# BRIDGE-ACCELEROMETER.net
KiCad netlist of a schematic drawn in Altium Designer
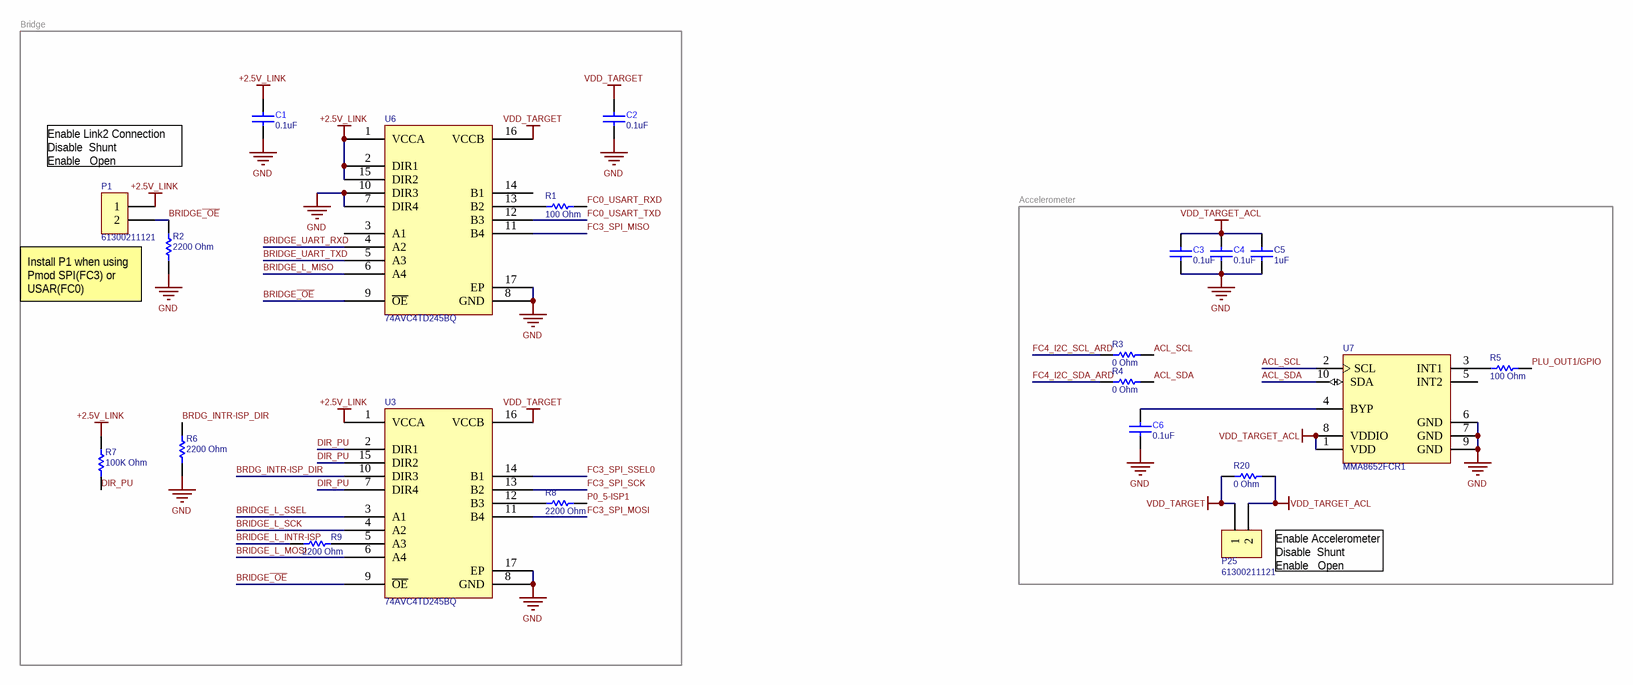
[diagram p0: BRIDGE-ACCELEROMETER.SchDoc]

(export (version "E")
  (design (tool "Eeschema 10.0.6"))
  (components
    (comp (ref "C1")
      (value "0.1uF")
      (footprint "CAPC1005")
      (description "Capacitor, Yageo, Ceramic, 0.1uF 10% 16V 0402 (1005) X7R")
      (fields
        (field (name "TOLERANCE") "10 %")
        (field (name "Comment") "CC0402KRX7R7BB104")
        (field (name "PUBLISHER") "Altium")
      )
      (libsource (lib "Altium Content Vault") (part "CMP-0001-00074-1"))
    )
    (comp (ref "C2")
      (value "0.1uF")
      (footprint "CAPC1005")
      (description "Capacitor, Yageo, Ceramic, 0.1uF 10% 16V 0402 (1005) X7R")
      (fields
        (field (name "TOLERANCE") "10 %")
        (field (name "Comment") "CC0402KRX7R7BB104")
        (field (name "PUBLISHER") "Altium")
      )
      (libsource (lib "Altium Content Vault") (part "CMP-0001-00074-1"))
    )
    (comp (ref "C3")
      (value "0.1uF")
      (footprint "CAPC1005")
      (description "Capacitor, Yageo, Ceramic, 0.1uF 10% 16V 0402 (1005) X7R")
      (fields
        (field (name "TOLERANCE") "10 %")
        (field (name "Comment") "CC0402KRX7R7BB104")
        (field (name "PUBLISHER") "Altium")
      )
      (libsource (lib "Altium Content Vault") (part "CMP-0001-00074-1"))
    )
    (comp (ref "C4")
      (value "0.1uF")
      (footprint "CAPC1005")
      (description "Capacitor, Yageo, Ceramic, 0.1uF 10% 16V 0402 (1005) X7R")
      (fields
        (field (name "TOLERANCE") "10 %")
        (field (name "Comment") "CC0402KRX7R7BB104")
        (field (name "PUBLISHER") "Altium")
      )
      (libsource (lib "Altium Content Vault") (part "CMP-0001-00074-1"))
    )
    (comp (ref "C5")
      (value "1uF")
      (footprint "CAPC0402(1005)60_L")
      (description "CAP 1uF 10V -20% to +80% 0402 (1005 Metric) Thickness 0.6mm SMD")
      (fields (field (name "TOLERANCE") "-20% to +80%") (field (name "Comment") "CAP 1uF 10V 0402(1005)"))
      (libsource (lib "Altium Content Vault") (part "CMP-1034-02118-1"))
    )
    (comp (ref "C6")
      (value "0.1uF")
      (footprint "CAPC1005")
      (description "Capacitor, Yageo, Ceramic, 0.1uF 10% 16V 0402 (1005) X7R")
      (fields
        (field (name "TOLERANCE") "10 %")
        (field (name "Comment") "CC0402KRX7R7BB104")
        (field (name "PUBLISHER") "Altium")
      )
      (libsource (lib "Altium Content Vault") (part "CMP-0001-00074-1"))
    )
    (comp (ref "P1")
      (value "61300211121")
      (footprint "61300211121")
      (description "HEADER 2POS SNGL T/H 2.54MM")
      (fields
        (field (name "MANUFACTURER") "Wurth Electronics Inc")
        (field (name "MODIFIED BY") "*")
        (field (name "CREATED BY") "gmoreno")
      )
      (libsource (lib "") (part "61300211121_1"))
    )
    (comp (ref "P25")
      (value "61300211121")
      (footprint "61300211121")
      (description "HEADER 2POS SNGL T/H 2.54MM")
      (fields
        (field (name "MANUFACTURER") "Wurth Electronics Inc")
        (field (name "MODIFIED BY") "*")
        (field (name "CREATED BY") "gmoreno")
      )
      (libsource (lib "Rectangular - Headers, Male Pins") (part "61300211121"))
    )
    (comp (ref "R1")
      (value "100 Ohm")
      (footprint "RESC0402(1005)_L")
      (description "100R 0.063W 5% 0402 (1005 Metric)  SMD")
      (fields (field (name "POWER") "0.063 W") (field (name "TOLERANCE") "5 %"))
      (libsource (lib "Altium Content Vault") (part "CMP-1011-00050-1"))
    )
    (comp (ref "R2")
      (value "2200 Ohm")
      (footprint "RESC0402(1005)_L")
      (description "2K2 0.063W 1% 0402 (1005 Metric)  SMD")
      (fields (field (name "POWER") "0.063 W") (field (name "TOLERANCE") "1 %"))
      (libsource (lib "Altium Content Vault") (part "CMP-1011-00546-1"))
    )
    (comp (ref "R3")
      (value "0 Ohm")
      (footprint "RESC0402(1005)_L")
      (description "Jumper 0402 (1005 Metric)")
      (fields (field (name "TOLERANCE") "None") (field (name "Comment") "Jumper 0402(1005)"))
      (libsource (lib "Altium Content Vault") (part "CMP-1011-00001-1"))
    )
    (comp (ref "R4")
      (value "0 Ohm")
      (footprint "RESC0402(1005)_L")
      (description "Jumper 0402 (1005 Metric)")
      (fields (field (name "TOLERANCE") "None") (field (name "Comment") "Jumper 0402(1005)"))
      (libsource (lib "Altium Content Vault") (part "CMP-1011-00001-1"))
    )
    (comp (ref "R5")
      (value "100 Ohm")
      (footprint "RESC0402(1005)_L")
      (description "100R 0.063W 5% 0402 (1005 Metric)  SMD")
      (fields (field (name "POWER") "0.063 W") (field (name "TOLERANCE") "5 %"))
      (libsource (lib "Altium Content Vault") (part "CMP-1011-00050-1"))
    )
    (comp (ref "R6")
      (value "2200 Ohm")
      (footprint "RESC0402(1005)_L")
      (description "2K2 0.063W 1% 0402 (1005 Metric)  SMD")
      (fields (field (name "POWER") "0.063 W") (field (name "TOLERANCE") "1 %"))
      (libsource (lib "Altium Content Vault") (part "CMP-1011-00546-1"))
    )
    (comp (ref "R7")
      (value "100K Ohm")
      (footprint "RESC1005X40X25LL05T05")
      (description "Chip Resistor, 100 KOhm, +/- 1%, 100 mW, -55 to 155 degC, 0402 (1005 Metric), RoHS, Tape and Reel")
      (fields (field (name "TOLERANCE") "1%") (field (name "MANUFACTURER") "Basic Passives"))
      (libsource (lib "Altium Content Vault") (part "CMP-2002-00608-3"))
    )
    (comp (ref "R8")
      (value "2200 Ohm")
      (footprint "RESC0402(1005)_L")
      (description "2K2 0.063W 1% 0402 (1005 Metric)  SMD")
      (fields (field (name "POWER") "0.063 W") (field (name "TOLERANCE") "1 %"))
      (libsource (lib "Altium Content Vault") (part "CMP-1011-00546-1"))
    )
    (comp (ref "R9")
      (value "2200 Ohm")
      (footprint "RESC0402(1005)_L")
      (description "2K2 0.063W 1% 0402 (1005 Metric)  SMD")
      (fields (field (name "POWER") "0.063 W") (field (name "TOLERANCE") "1 %"))
      (libsource (lib "Altium Content Vault") (part "CMP-1011-00546-1"))
    )
    (comp (ref "R20")
      (value "0 Ohm")
      (footprint "RESC0402(1005)_L")
      (description "Jumper 0402 (1005 Metric)")
      (fields (field (name "TOLERANCE") "None") (field (name "Comment") "Jumper 0402(1005)"))
      (libsource (lib "Altium Content Vault") (part "CMP-1011-00001-1"))
    )
    (comp (ref "U3")
      (value "74AVC4TD245BQ")
      (footprint "DHVQFN16 (NXP)")
      (description "TXRX 4BIT DUAL 3STATE 16-DHVQFN")
      (fields
        (field (name "MANUFACTURER") "NXP Semiconductors")
        (field (name "CREATED BY") "Jose")
        (field (name "MODIFIED BY") "*")
      )
      (libsource (lib "Logic - Translators") (part "74AVC4TD245BQ"))
    )
    (comp (ref "U6")
      (value "74AVC4TD245BQ")
      (footprint "DHVQFN16 (NXP)")
      (description "TXRX 4BIT DUAL 3STATE 16-DHVQFN")
      (fields
        (field (name "MANUFACTURER") "NXP Semiconductors")
        (field (name "CREATED BY") "Jose")
        (field (name "MODIFIED BY") "*")
      )
      (libsource (lib "Logic - Translators") (part "74AVC4TD245BQ"))
    )
    (comp (ref "U7")
      (value "MMA8652FCR1")
      (footprint "FRES-2162-02_V")
      (fields (field (name "MANUFACTURER") "Freescale Semiconductor"))
      (libsource (lib "Altium Content Vault") (part "CMP-1356-00001-1"))
    )
  )
  (nets
    (net (code "1") (name "+2.5V_LINK") (class "Default")
      (node (ref "C1") (pin "1") (pinfunction "1_1") (pintype "passive"))
      (node (ref "P1") (pin "1") (pinfunction "1_1") (pintype "passive"))
      (node (ref "R7") (pin "2") (pinfunction "2_2") (pintype "passive"))
      (node (ref "U3") (pin "1") (pinfunction "VCCA_1") (pintype "passive"))
      (node (ref "U6") (pin "1") (pinfunction "VCCA_1") (pintype "passive"))
      (node (ref "U6") (pin "15") (pinfunction "DIR2_15") (pintype "passive"))
      (node (ref "U6") (pin "2") (pinfunction "DIR1_2") (pintype "passive"))
    )
    (net (code "2") (name "/ACL_SCL") (class "Default")
      (node (ref "R3") (pin "1") (pinfunction "1_1") (pintype "passive"))
      (node (ref "U7") (pin "2") (pinfunction "SCL_2") (pintype "passive"))
    )
    (net (code "3") (name "/ACL_SDA") (class "Default")
      (node (ref "R4") (pin "1") (pinfunction "1_1") (pintype "passive"))
      (node (ref "U7") (pin "10") (pinfunction "SDA_10") (pintype "bidirectional"))
    )
    (net (code "4") (name "/BRDG_INTR-ISP_DIR") (class "Default")
      (node (ref "R6") (pin "2") (pinfunction "2_2") (pintype "passive"))
      (node (ref "U3") (pin "10") (pinfunction "DIR3_10") (pintype "passive"))
    )
    (net (code "5") (name "/BRIDGE_L_INTR-ISP") (class "Default")
      (node (ref "R9") (pin "2") (pinfunction "2_2") (pintype "passive"))
    )
    (net (code "6") (name "/BRIDGE_L_MISO") (class "Default")
      (node (ref "U6") (pin "6") (pinfunction "A4_6") (pintype "passive"))
    )
    (net (code "7") (name "/BRIDGE_L_MOSI") (class "Default")
      (node (ref "U3") (pin "6") (pinfunction "A4_6") (pintype "passive"))
    )
    (net (code "8") (name "/BRIDGE_L_SCK") (class "Default")
      (node (ref "U3") (pin "4") (pinfunction "A2_4") (pintype "passive"))
    )
    (net (code "9") (name "/BRIDGE_L_SSEL") (class "Default")
      (node (ref "U3") (pin "3") (pinfunction "A1_3") (pintype "passive"))
    )
    (net (code "10") (name "/BRIDGE_UART_RXD") (class "Default")
      (node (ref "U6") (pin "4") (pinfunction "A2_4") (pintype "passive"))
    )
    (net (code "11") (name "/BRIDGE_UART_TXD") (class "Default")
      (node (ref "U6") (pin "5") (pinfunction "A3_5") (pintype "passive"))
    )
    (net (code "12") (name "/BRIDGE~{_OE}") (class "Default")
      (node (ref "P1") (pin "2") (pinfunction "2_2") (pintype "passive"))
      (node (ref "R2") (pin "1") (pinfunction "1_1") (pintype "passive"))
      (node (ref "U3") (pin "9") (pinfunction "~{OE}_9") (pintype "passive"))
      (node (ref "U6") (pin "9") (pinfunction "~{OE}_9") (pintype "passive"))
    )
    (net (code "13") (name "/DIR_PU") (class "Default")
      (node (ref "R7") (pin "1") (pinfunction "1_1") (pintype "passive"))
      (node (ref "U3") (pin "15") (pinfunction "DIR2_15") (pintype "passive"))
      (node (ref "U3") (pin "2") (pinfunction "DIR1_2") (pintype "passive"))
      (node (ref "U3") (pin "7") (pinfunction "DIR4_7") (pintype "passive"))
    )
    (net (code "14") (name "/FC0_USART_RXD") (class "Default")
      (node (ref "R1") (pin "2") (pinfunction "2_2") (pintype "passive"))
    )
    (net (code "15") (name "/FC0_USART_TXD") (class "Default")
      (node (ref "U6") (pin "12") (pinfunction "B3_12") (pintype "passive"))
    )
    (net (code "16") (name "/FC3_SPI_MISO") (class "Default")
      (node (ref "U6") (pin "11") (pinfunction "B4_11") (pintype "passive"))
    )
    (net (code "17") (name "/FC3_SPI_MOSI") (class "Default")
      (node (ref "U3") (pin "11") (pinfunction "B4_11") (pintype "passive"))
    )
    (net (code "18") (name "/FC3_SPI_SCK") (class "Default")
      (node (ref "U3") (pin "13") (pinfunction "B2_13") (pintype "passive"))
    )
    (net (code "19") (name "/FC3_SPI_SSEL0") (class "Default")
      (node (ref "U3") (pin "14") (pinfunction "B1_14") (pintype "passive"))
    )
    (net (code "20") (name "/FC4_I2C_SCL_ARD") (class "Default")
      (node (ref "R3") (pin "2") (pinfunction "2_2") (pintype "passive"))
    )
    (net (code "21") (name "/FC4_I2C_SDA_ARD") (class "Default")
      (node (ref "R4") (pin "2") (pinfunction "2_2") (pintype "passive"))
    )
    (net (code "22") (name "/P0_5-ISP1") (class "Default")
      (node (ref "R8") (pin "1") (pinfunction "1_1") (pintype "passive"))
    )
    (net (code "23") (name "/PLU_OUT1{slash}GPIO") (class "Default")
      (node (ref "R5") (pin "2") (pinfunction "2_2") (pintype "passive"))
    )
    (net (code "24") (name "GND") (class "Default")
      (node (ref "C1") (pin "2") (pinfunction "2_2") (pintype "passive"))
      (node (ref "C2") (pin "2") (pinfunction "2_2") (pintype "passive"))
      (node (ref "C3") (pin "2") (pinfunction "2_2") (pintype "passive"))
      (node (ref "C4") (pin "2") (pinfunction "2_2") (pintype "passive"))
      (node (ref "C5") (pin "1") (pinfunction "1_1") (pintype "passive"))
      (node (ref "C6") (pin "2") (pinfunction "2_2") (pintype "passive"))
      (node (ref "R2") (pin "2") (pinfunction "2_2") (pintype "passive"))
      (node (ref "R6") (pin "1") (pinfunction "1_1") (pintype "passive"))
      (node (ref "U3") (pin "17") (pinfunction "EP_17") (pintype "passive"))
      (node (ref "U3") (pin "8") (pinfunction "GND_8") (pintype "passive"))
      (node (ref "U6") (pin "10") (pinfunction "DIR3_10") (pintype "passive"))
      (node (ref "U6") (pin "17") (pinfunction "EP_17") (pintype "passive"))
      (node (ref "U6") (pin "7") (pinfunction "DIR4_7") (pintype "passive"))
      (node (ref "U6") (pin "8") (pinfunction "GND_8") (pintype "passive"))
      (node (ref "U7") (pin "6") (pinfunction "GND_6") (pintype "power_in"))
      (node (ref "U7") (pin "7") (pinfunction "GND_7") (pintype "power_in"))
      (node (ref "U7") (pin "9") (pinfunction "GND_9") (pintype "power_in"))
    )
    (net (code "25") (name "Net-(U3-A3)") (class "Default")
      (node (ref "R9") (pin "1") (pinfunction "1_1") (pintype "passive"))
      (node (ref "U3") (pin "5") (pinfunction "A3_5") (pintype "passive"))
    )
    (net (code "26") (name "Net-(U3-B3)") (class "Default")
      (node (ref "R8") (pin "2") (pinfunction "2_2") (pintype "passive"))
      (node (ref "U3") (pin "12") (pinfunction "B3_12") (pintype "passive"))
    )
    (net (code "27") (name "Net-(U6-B2)") (class "Default")
      (node (ref "R1") (pin "1") (pinfunction "1_1") (pintype "passive"))
      (node (ref "U6") (pin "13") (pinfunction "B2_13") (pintype "passive"))
    )
    (net (code "28") (name "Net-(U7-BYP)") (class "Default")
      (node (ref "C6") (pin "1") (pinfunction "1_1") (pintype "passive"))
      (node (ref "U7") (pin "4") (pinfunction "BYP_4") (pintype "passive"))
    )
    (net (code "29") (name "Net-(U7-INT1)") (class "Default")
      (node (ref "R5") (pin "1") (pinfunction "1_1") (pintype "passive"))
      (node (ref "U7") (pin "3") (pinfunction "INT1_3") (pintype "open_collector"))
    )
    (net (code "30") (name "VDD_TARGET") (class "Default")
      (node (ref "C2") (pin "1") (pinfunction "1_1") (pintype "passive"))
      (node (ref "P25") (pin "1") (pinfunction "1_1") (pintype "passive"))
      (node (ref "R20") (pin "2") (pinfunction "2_2") (pintype "passive"))
      (node (ref "U3") (pin "16") (pinfunction "VCCB_16") (pintype "passive"))
      (node (ref "U6") (pin "16") (pinfunction "VCCB_16") (pintype "passive"))
    )
    (net (code "31") (name "VDD_TARGET_ACL") (class "Default")
      (node (ref "C3") (pin "1") (pinfunction "1_1") (pintype "passive"))
      (node (ref "C4") (pin "1") (pinfunction "1_1") (pintype "passive"))
      (node (ref "C5") (pin "2") (pinfunction "2_2") (pintype "passive"))
      (node (ref "P25") (pin "2") (pinfunction "2_2") (pintype "passive"))
      (node (ref "R20") (pin "1") (pinfunction "1_1") (pintype "passive"))
      (node (ref "U7") (pin "1") (pinfunction "VDD_1") (pintype "power_in"))
      (node (ref "U7") (pin "8") (pinfunction "VDDIO_8") (pintype "power_in"))
    )
    (net (code "32") (name "unconnected-(U6-A1-Pad3)") (class "Default")
      (node (ref "U6") (pin "3") (pinfunction "A1_3") (pintype "passive"))
    )
    (net (code "33") (name "unconnected-(U6-B1-Pad14)") (class "Default")
      (node (ref "U6") (pin "14") (pinfunction "B1_14") (pintype "passive"))
    )
    (net (code "34") (name "unconnected-(U7-INT2-Pad5)") (class "Default")
      (node (ref "U7") (pin "5") (pinfunction "INT2_5") (pintype "open_collector"))
    )
  )
)
